# Level_Shift.net
KiCad netlist of a schematic drawn in EAGLE
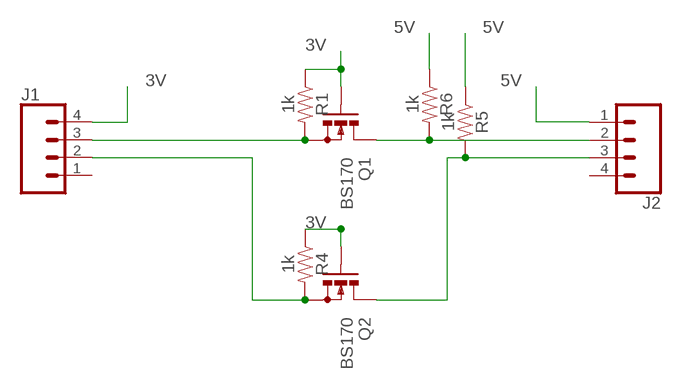
[diagram p0: schematic, sheet 1]

(export (version "E")
  (design (tool "Eeschema 10.0.6"))
  (components
    (comp (ref "J1")
      (value "CONN_04")
      (footprint "eagle-import:1X04")
      (libsource (lib "eagle-import") (part "CONN_04"))
    )
    (comp (ref "J2")
      (value "CONN_04")
      (footprint "eagle-import:1X04")
      (libsource (lib "eagle-import") (part "CONN_04"))
    )
    (comp (ref "Q1")
      (value "BS170")
      (footprint "eagle-import:SOT54E")
      (libsource (lib "eagle-import") (part "BS170"))
    )
    (comp (ref "Q2")
      (value "BS170")
      (footprint "eagle-import:SOT54E")
      (libsource (lib "eagle-import") (part "BS170"))
    )
    (comp (ref "R1")
      (value "1k")
      (footprint "eagle-import:AXIAL-0.3")
      (libsource (lib "eagle-import") (part "1KOHM-HORIZ-1/4W-1%"))
    )
    (comp (ref "R4")
      (value "1k")
      (footprint "eagle-import:AXIAL-0.3")
      (libsource (lib "eagle-import") (part "1KOHM-HORIZ-1/4W-1%"))
    )
    (comp (ref "R5")
      (value "1k")
      (footprint "eagle-import:AXIAL-0.3")
      (libsource (lib "eagle-import") (part "1KOHM-HORIZ-1/4W-1%"))
    )
    (comp (ref "R6")
      (value "1k")
      (footprint "eagle-import:AXIAL-0.3")
      (libsource (lib "eagle-import") (part "1KOHM-HORIZ-1/4W-1%"))
    )
  )
  (nets
    (net (code "1") (name "/3V") (class "Default")
      (node (ref "J1") (pin "4") (pinfunction "4_4") (pintype "passive"))
      (node (ref "Q1") (pin "G") (pinfunction "G_G") (pintype "passive"))
      (node (ref "Q2") (pin "G") (pinfunction "G_G") (pintype "passive"))
      (node (ref "R1") (pin "P$1") (pinfunction "1_P$1") (pintype "passive"))
      (node (ref "R4") (pin "P$1") (pinfunction "1_P$1") (pintype "passive"))
    )
    (net (code "2") (name "/5V") (class "Default")
      (node (ref "J2") (pin "1") (pinfunction "1_1") (pintype "passive"))
      (node (ref "R5") (pin "P$1") (pinfunction "1_P$1") (pintype "passive"))
      (node (ref "R6") (pin "P$1") (pinfunction "1_P$1") (pintype "passive"))
    )
    (net (code "3") (name "Net-(R1-2)") (class "Default")
      (node (ref "J1") (pin "3") (pinfunction "3_3") (pintype "passive"))
      (node (ref "Q1") (pin "S") (pinfunction "S_S") (pintype "passive"))
      (node (ref "R1") (pin "P$2") (pinfunction "2_P$2") (pintype "passive"))
    )
    (net (code "4") (name "Net-(R4-2)") (class "Default")
      (node (ref "J1") (pin "2") (pinfunction "2_2") (pintype "passive"))
      (node (ref "Q2") (pin "S") (pinfunction "S_S") (pintype "passive"))
      (node (ref "R4") (pin "P$2") (pinfunction "2_P$2") (pintype "passive"))
    )
    (net (code "5") (name "Net-(R5-2)") (class "Default")
      (node (ref "J2") (pin "3") (pinfunction "3_3") (pintype "passive"))
      (node (ref "Q2") (pin "D") (pinfunction "D_D") (pintype "passive"))
      (node (ref "R5") (pin "P$2") (pinfunction "2_P$2") (pintype "passive"))
    )
    (net (code "6") (name "Net-(R6-2)") (class "Default")
      (node (ref "J2") (pin "2") (pinfunction "2_2") (pintype "passive"))
      (node (ref "Q1") (pin "D") (pinfunction "D_D") (pintype "passive"))
      (node (ref "R6") (pin "P$2") (pinfunction "2_P$2") (pintype "passive"))
    )
    (net (code "7") (name "unconnected-(J1-Pad1)") (class "Default")
      (node (ref "J1") (pin "1") (pinfunction "1_1") (pintype "passive"))
    )
    (net (code "8") (name "unconnected-(J2-Pad4)") (class "Default")
      (node (ref "J2") (pin "4") (pinfunction "4_4") (pintype "passive"))
    )
  )
)
